# 001-0002_beaglebone_cape_board.net
KiCad netlist of a schematic drawn in Altium Designer
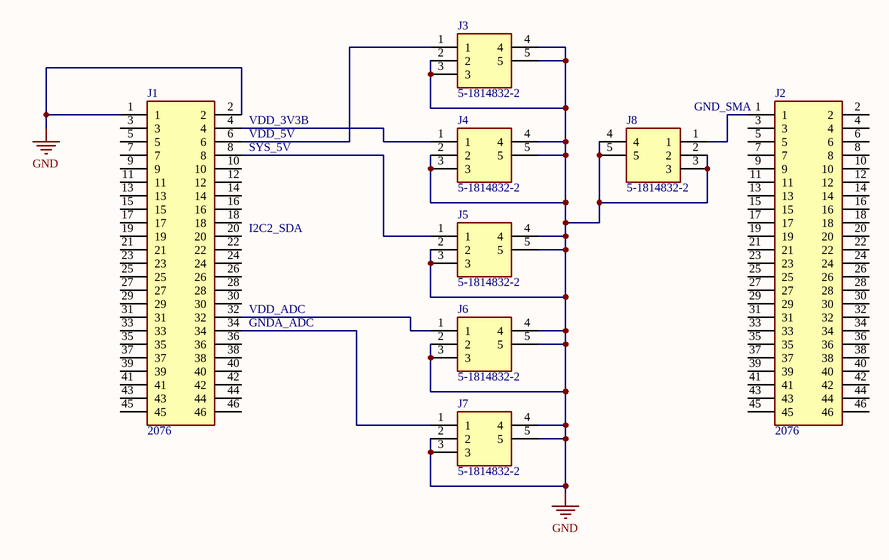
[diagram p0: 001-0002_beaglebone_cape_board.SchDoc]

(export (version "E")
  (design (tool "Eeschema 10.0.6"))
  (components
    (comp (ref "J1")
      (value "2076")
      (footprint "HDRV46W64P254_2X23_5842X500X874P")
      (description "Adafruit Accessories 2x23 Male Headers for BeagleBone Black - Two Pack")
      (fields (field (name "MOUSER PART NUMBER") "485-2076"))
      (libsource (lib "default") (part "2076"))
    )
    (comp (ref "J2")
      (value "2076")
      (footprint "HDRV46W64P254_2X23_5842X500X874P")
      (description "Adafruit Accessories 2x23 Male Headers for BeagleBone Black - Two Pack")
      (fields (field (name "MOUSER PART NUMBER") "485-2076"))
      (libsource (lib "default") (part "2076"))
    )
    (comp (ref "J3")
      (value "5-1814832-2")
      (footprint "5-1814832-2")
      (description "SMA Connector Jack, Female Socket 50 Ohms Through Hole Solder")
      (fields (field (name "MOUSER PART NUMBER") "571-5-1814832-2"))
      (libsource (lib "") (part "5-1814832-2_1"))
    )
    (comp (ref "J4")
      (value "5-1814832-2")
      (footprint "5-1814832-2")
      (description "SMA Connector Jack, Female Socket 50 Ohms Through Hole Solder")
      (fields (field (name "MOUSER PART NUMBER") "571-5-1814832-2"))
      (libsource (lib "") (part "5-1814832-2_1"))
    )
    (comp (ref "J5")
      (value "5-1814832-2")
      (footprint "5-1814832-2")
      (description "SMA Connector Jack, Female Socket 50 Ohms Through Hole Solder")
      (fields (field (name "MOUSER PART NUMBER") "571-5-1814832-2"))
      (libsource (lib "") (part "5-1814832-2_1"))
    )
    (comp (ref "J6")
      (value "5-1814832-2")
      (footprint "5-1814832-2")
      (description "SMA Connector Jack, Female Socket 50 Ohms Through Hole Solder")
      (fields (field (name "MOUSER PART NUMBER") "571-5-1814832-2"))
      (libsource (lib "") (part "5-1814832-2_1"))
    )
    (comp (ref "J7")
      (value "5-1814832-2")
      (footprint "5-1814832-2")
      (description "SMA Connector Jack, Female Socket 50 Ohms Through Hole Solder")
      (fields (field (name "MOUSER PART NUMBER") "571-5-1814832-2"))
      (libsource (lib "") (part "5-1814832-2_1"))
    )
    (comp (ref "J8")
      (value "5-1814832-2")
      (footprint "5-1814832-2")
      (description "SMA Connector Jack, Female Socket 50 Ohms Through Hole Solder")
      (fields (field (name "MOUSER PART NUMBER") "571-5-1814832-2"))
      (libsource (lib "default") (part "5-1814832-2"))
    )
  )
  (nets
    (net (code "1") (name "GND") (class "Default")
      (node (ref "J1") (pin "1") (pinfunction "1_1") (pintype "passive"))
      (node (ref "J1") (pin "2") (pinfunction "2_2") (pintype "passive"))
      (node (ref "J3") (pin "2") (pinfunction "2_2") (pintype "passive"))
      (node (ref "J3") (pin "3") (pinfunction "3_3") (pintype "passive"))
      (node (ref "J3") (pin "4") (pinfunction "4_4") (pintype "passive"))
      (node (ref "J3") (pin "5") (pinfunction "5_5") (pintype "passive"))
      (node (ref "J4") (pin "2") (pinfunction "2_2") (pintype "passive"))
      (node (ref "J4") (pin "3") (pinfunction "3_3") (pintype "passive"))
      (node (ref "J4") (pin "4") (pinfunction "4_4") (pintype "passive"))
      (node (ref "J4") (pin "5") (pinfunction "5_5") (pintype "passive"))
      (node (ref "J5") (pin "2") (pinfunction "2_2") (pintype "passive"))
      (node (ref "J5") (pin "3") (pinfunction "3_3") (pintype "passive"))
      (node (ref "J5") (pin "4") (pinfunction "4_4") (pintype "passive"))
      (node (ref "J5") (pin "5") (pinfunction "5_5") (pintype "passive"))
      (node (ref "J6") (pin "2") (pinfunction "2_2") (pintype "passive"))
      (node (ref "J6") (pin "3") (pinfunction "3_3") (pintype "passive"))
      (node (ref "J6") (pin "4") (pinfunction "4_4") (pintype "passive"))
      (node (ref "J6") (pin "5") (pinfunction "5_5") (pintype "passive"))
      (node (ref "J7") (pin "2") (pinfunction "2_2") (pintype "passive"))
      (node (ref "J7") (pin "3") (pinfunction "3_3") (pintype "passive"))
      (node (ref "J7") (pin "4") (pinfunction "4_4") (pintype "passive"))
      (node (ref "J7") (pin "5") (pinfunction "5_5") (pintype "passive"))
      (node (ref "J8") (pin "2") (pinfunction "2_2") (pintype "passive"))
      (node (ref "J8") (pin "3") (pinfunction "3_3") (pintype "passive"))
      (node (ref "J8") (pin "4") (pinfunction "4_4") (pintype "passive"))
      (node (ref "J8") (pin "5") (pinfunction "5_5") (pintype "passive"))
    )
    (net (code "2") (name "Net-(J1-Pad4)") (class "Default")
      (node (ref "J1") (pin "4") (pinfunction "4_4") (pintype "passive"))
      (node (ref "J4") (pin "1") (pinfunction "1_1") (pintype "passive"))
    )
    (net (code "3") (name "Net-(J1-Pad6)") (class "Default")
      (node (ref "J1") (pin "6") (pinfunction "6_6") (pintype "passive"))
      (node (ref "J3") (pin "1") (pinfunction "1_1") (pintype "passive"))
    )
    (net (code "4") (name "Net-(J1-Pad8)") (class "Default")
      (node (ref "J1") (pin "8") (pinfunction "8_8") (pintype "passive"))
      (node (ref "J5") (pin "1") (pinfunction "1_1") (pintype "passive"))
    )
    (net (code "5") (name "Net-(J1-Pad32)") (class "Default")
      (node (ref "J1") (pin "32") (pinfunction "32_32") (pintype "passive"))
      (node (ref "J6") (pin "1") (pinfunction "1_1") (pintype "passive"))
    )
    (net (code "6") (name "Net-(J1-Pad34)") (class "Default")
      (node (ref "J1") (pin "34") (pinfunction "34_34") (pintype "passive"))
      (node (ref "J7") (pin "1") (pinfunction "1_1") (pintype "passive"))
    )
    (net (code "7") (name "Net-(J2-Pad1)") (class "Default")
      (node (ref "J2") (pin "1") (pinfunction "1_1") (pintype "passive"))
      (node (ref "J8") (pin "1") (pinfunction "1_1") (pintype "passive"))
    )
    (net (code "8") (name "unconnected-(J1-Pad3)") (class "Default")
      (node (ref "J1") (pin "3") (pinfunction "3_3") (pintype "passive"))
    )
    (net (code "9") (name "unconnected-(J1-Pad5)") (class "Default")
      (node (ref "J1") (pin "5") (pinfunction "5_5") (pintype "passive"))
    )
    (net (code "10") (name "unconnected-(J1-Pad7)") (class "Default")
      (node (ref "J1") (pin "7") (pinfunction "7_7") (pintype "passive"))
    )
    (net (code "11") (name "unconnected-(J1-Pad9)") (class "Default")
      (node (ref "J1") (pin "9") (pinfunction "9_9") (pintype "passive"))
    )
    (net (code "12") (name "unconnected-(J1-Pad10)") (class "Default")
      (node (ref "J1") (pin "10") (pinfunction "10_10") (pintype "passive"))
    )
    (net (code "13") (name "unconnected-(J1-Pad11)") (class "Default")
      (node (ref "J1") (pin "11") (pinfunction "11_11") (pintype "passive"))
    )
    (net (code "14") (name "unconnected-(J1-Pad12)") (class "Default")
      (node (ref "J1") (pin "12") (pinfunction "12_12") (pintype "passive"))
    )
    (net (code "15") (name "unconnected-(J1-Pad13)") (class "Default")
      (node (ref "J1") (pin "13") (pinfunction "13_13") (pintype "passive"))
    )
    (net (code "16") (name "unconnected-(J1-Pad14)") (class "Default")
      (node (ref "J1") (pin "14") (pinfunction "14_14") (pintype "passive"))
    )
    (net (code "17") (name "unconnected-(J1-Pad15)") (class "Default")
      (node (ref "J1") (pin "15") (pinfunction "15_15") (pintype "passive"))
    )
    (net (code "18") (name "unconnected-(J1-Pad16)") (class "Default")
      (node (ref "J1") (pin "16") (pinfunction "16_16") (pintype "passive"))
    )
    (net (code "19") (name "unconnected-(J1-Pad17)") (class "Default")
      (node (ref "J1") (pin "17") (pinfunction "17_17") (pintype "passive"))
    )
    (net (code "20") (name "unconnected-(J1-Pad18)") (class "Default")
      (node (ref "J1") (pin "18") (pinfunction "18_18") (pintype "passive"))
    )
    (net (code "21") (name "unconnected-(J1-Pad19)") (class "Default")
      (node (ref "J1") (pin "19") (pinfunction "19_19") (pintype "passive"))
    )
    (net (code "22") (name "unconnected-(J1-Pad20)") (class "Default")
      (node (ref "J1") (pin "20") (pinfunction "20_20") (pintype "passive"))
    )
    (net (code "23") (name "unconnected-(J1-Pad21)") (class "Default")
      (node (ref "J1") (pin "21") (pinfunction "21_21") (pintype "passive"))
    )
    (net (code "24") (name "unconnected-(J1-Pad22)") (class "Default")
      (node (ref "J1") (pin "22") (pinfunction "22_22") (pintype "passive"))
    )
    (net (code "25") (name "unconnected-(J1-Pad23)") (class "Default")
      (node (ref "J1") (pin "23") (pinfunction "23_23") (pintype "passive"))
    )
    (net (code "26") (name "unconnected-(J1-Pad24)") (class "Default")
      (node (ref "J1") (pin "24") (pinfunction "24_24") (pintype "passive"))
    )
    (net (code "27") (name "unconnected-(J1-Pad25)") (class "Default")
      (node (ref "J1") (pin "25") (pinfunction "25_25") (pintype "passive"))
    )
    (net (code "28") (name "unconnected-(J1-Pad26)") (class "Default")
      (node (ref "J1") (pin "26") (pinfunction "26_26") (pintype "passive"))
    )
    (net (code "29") (name "unconnected-(J1-Pad27)") (class "Default")
      (node (ref "J1") (pin "27") (pinfunction "27_27") (pintype "passive"))
    )
    (net (code "30") (name "unconnected-(J1-Pad28)") (class "Default")
      (node (ref "J1") (pin "28") (pinfunction "28_28") (pintype "passive"))
    )
    (net (code "31") (name "unconnected-(J1-Pad29)") (class "Default")
      (node (ref "J1") (pin "29") (pinfunction "29_29") (pintype "passive"))
    )
    (net (code "32") (name "unconnected-(J1-Pad30)") (class "Default")
      (node (ref "J1") (pin "30") (pinfunction "30_30") (pintype "passive"))
    )
    (net (code "33") (name "unconnected-(J1-Pad31)") (class "Default")
      (node (ref "J1") (pin "31") (pinfunction "31_31") (pintype "passive"))
    )
    (net (code "34") (name "unconnected-(J1-Pad33)") (class "Default")
      (node (ref "J1") (pin "33") (pinfunction "33_33") (pintype "passive"))
    )
    (net (code "35") (name "unconnected-(J1-Pad35)") (class "Default")
      (node (ref "J1") (pin "35") (pinfunction "35_35") (pintype "passive"))
    )
    (net (code "36") (name "unconnected-(J1-Pad36)") (class "Default")
      (node (ref "J1") (pin "36") (pinfunction "36_36") (pintype "passive"))
    )
    (net (code "37") (name "unconnected-(J1-Pad37)") (class "Default")
      (node (ref "J1") (pin "37") (pinfunction "37_37") (pintype "passive"))
    )
    (net (code "38") (name "unconnected-(J1-Pad38)") (class "Default")
      (node (ref "J1") (pin "38") (pinfunction "38_38") (pintype "passive"))
    )
    (net (code "39") (name "unconnected-(J1-Pad39)") (class "Default")
      (node (ref "J1") (pin "39") (pinfunction "39_39") (pintype "passive"))
    )
    (net (code "40") (name "unconnected-(J1-Pad40)") (class "Default")
      (node (ref "J1") (pin "40") (pinfunction "40_40") (pintype "passive"))
    )
    (net (code "41") (name "unconnected-(J1-Pad41)") (class "Default")
      (node (ref "J1") (pin "41") (pinfunction "41_41") (pintype "passive"))
    )
    (net (code "42") (name "unconnected-(J1-Pad42)") (class "Default")
      (node (ref "J1") (pin "42") (pinfunction "42_42") (pintype "passive"))
    )
    (net (code "43") (name "unconnected-(J1-Pad43)") (class "Default")
      (node (ref "J1") (pin "43") (pinfunction "43_43") (pintype "passive"))
    )
    (net (code "44") (name "unconnected-(J1-Pad44)") (class "Default")
      (node (ref "J1") (pin "44") (pinfunction "44_44") (pintype "passive"))
    )
    (net (code "45") (name "unconnected-(J1-Pad45)") (class "Default")
      (node (ref "J1") (pin "45") (pinfunction "45_45") (pintype "passive"))
    )
    (net (code "46") (name "unconnected-(J1-Pad46)") (class "Default")
      (node (ref "J1") (pin "46") (pinfunction "46_46") (pintype "passive"))
    )
    (net (code "47") (name "unconnected-(J2-Pad2)") (class "Default")
      (node (ref "J2") (pin "2") (pinfunction "2_2") (pintype "passive"))
    )
    (net (code "48") (name "unconnected-(J2-Pad3)") (class "Default")
      (node (ref "J2") (pin "3") (pinfunction "3_3") (pintype "passive"))
    )
    (net (code "49") (name "unconnected-(J2-Pad4)") (class "Default")
      (node (ref "J2") (pin "4") (pinfunction "4_4") (pintype "passive"))
    )
    (net (code "50") (name "unconnected-(J2-Pad5)") (class "Default")
      (node (ref "J2") (pin "5") (pinfunction "5_5") (pintype "passive"))
    )
    (net (code "51") (name "unconnected-(J2-Pad6)") (class "Default")
      (node (ref "J2") (pin "6") (pinfunction "6_6") (pintype "passive"))
    )
    (net (code "52") (name "unconnected-(J2-Pad7)") (class "Default")
      (node (ref "J2") (pin "7") (pinfunction "7_7") (pintype "passive"))
    )
    (net (code "53") (name "unconnected-(J2-Pad8)") (class "Default")
      (node (ref "J2") (pin "8") (pinfunction "8_8") (pintype "passive"))
    )
    (net (code "54") (name "unconnected-(J2-Pad9)") (class "Default")
      (node (ref "J2") (pin "9") (pinfunction "9_9") (pintype "passive"))
    )
    (net (code "55") (name "unconnected-(J2-Pad10)") (class "Default")
      (node (ref "J2") (pin "10") (pinfunction "10_10") (pintype "passive"))
    )
    (net (code "56") (name "unconnected-(J2-Pad11)") (class "Default")
      (node (ref "J2") (pin "11") (pinfunction "11_11") (pintype "passive"))
    )
    (net (code "57") (name "unconnected-(J2-Pad12)") (class "Default")
      (node (ref "J2") (pin "12") (pinfunction "12_12") (pintype "passive"))
    )
    (net (code "58") (name "unconnected-(J2-Pad13)") (class "Default")
      (node (ref "J2") (pin "13") (pinfunction "13_13") (pintype "passive"))
    )
    (net (code "59") (name "unconnected-(J2-Pad14)") (class "Default")
      (node (ref "J2") (pin "14") (pinfunction "14_14") (pintype "passive"))
    )
    (net (code "60") (name "unconnected-(J2-Pad15)") (class "Default")
      (node (ref "J2") (pin "15") (pinfunction "15_15") (pintype "passive"))
    )
    (net (code "61") (name "unconnected-(J2-Pad16)") (class "Default")
      (node (ref "J2") (pin "16") (pinfunction "16_16") (pintype "passive"))
    )
    (net (code "62") (name "unconnected-(J2-Pad17)") (class "Default")
      (node (ref "J2") (pin "17") (pinfunction "17_17") (pintype "passive"))
    )
    (net (code "63") (name "unconnected-(J2-Pad18)") (class "Default")
      (node (ref "J2") (pin "18") (pinfunction "18_18") (pintype "passive"))
    )
    (net (code "64") (name "unconnected-(J2-Pad19)") (class "Default")
      (node (ref "J2") (pin "19") (pinfunction "19_19") (pintype "passive"))
    )
    (net (code "65") (name "unconnected-(J2-Pad20)") (class "Default")
      (node (ref "J2") (pin "20") (pinfunction "20_20") (pintype "passive"))
    )
    (net (code "66") (name "unconnected-(J2-Pad21)") (class "Default")
      (node (ref "J2") (pin "21") (pinfunction "21_21") (pintype "passive"))
    )
    (net (code "67") (name "unconnected-(J2-Pad22)") (class "Default")
      (node (ref "J2") (pin "22") (pinfunction "22_22") (pintype "passive"))
    )
    (net (code "68") (name "unconnected-(J2-Pad23)") (class "Default")
      (node (ref "J2") (pin "23") (pinfunction "23_23") (pintype "passive"))
    )
    (net (code "69") (name "unconnected-(J2-Pad24)") (class "Default")
      (node (ref "J2") (pin "24") (pinfunction "24_24") (pintype "passive"))
    )
    (net (code "70") (name "unconnected-(J2-Pad25)") (class "Default")
      (node (ref "J2") (pin "25") (pinfunction "25_25") (pintype "passive"))
    )
    (net (code "71") (name "unconnected-(J2-Pad26)") (class "Default")
      (node (ref "J2") (pin "26") (pinfunction "26_26") (pintype "passive"))
    )
    (net (code "72") (name "unconnected-(J2-Pad27)") (class "Default")
      (node (ref "J2") (pin "27") (pinfunction "27_27") (pintype "passive"))
    )
    (net (code "73") (name "unconnected-(J2-Pad28)") (class "Default")
      (node (ref "J2") (pin "28") (pinfunction "28_28") (pintype "passive"))
    )
    (net (code "74") (name "unconnected-(J2-Pad29)") (class "Default")
      (node (ref "J2") (pin "29") (pinfunction "29_29") (pintype "passive"))
    )
    (net (code "75") (name "unconnected-(J2-Pad30)") (class "Default")
      (node (ref "J2") (pin "30") (pinfunction "30_30") (pintype "passive"))
    )
    (net (code "76") (name "unconnected-(J2-Pad31)") (class "Default")
      (node (ref "J2") (pin "31") (pinfunction "31_31") (pintype "passive"))
    )
    (net (code "77") (name "unconnected-(J2-Pad32)") (class "Default")
      (node (ref "J2") (pin "32") (pinfunction "32_32") (pintype "passive"))
    )
    (net (code "78") (name "unconnected-(J2-Pad33)") (class "Default")
      (node (ref "J2") (pin "33") (pinfunction "33_33") (pintype "passive"))
    )
    (net (code "79") (name "unconnected-(J2-Pad34)") (class "Default")
      (node (ref "J2") (pin "34") (pinfunction "34_34") (pintype "passive"))
    )
    (net (code "80") (name "unconnected-(J2-Pad35)") (class "Default")
      (node (ref "J2") (pin "35") (pinfunction "35_35") (pintype "passive"))
    )
    (net (code "81") (name "unconnected-(J2-Pad36)") (class "Default")
      (node (ref "J2") (pin "36") (pinfunction "36_36") (pintype "passive"))
    )
    (net (code "82") (name "unconnected-(J2-Pad37)") (class "Default")
      (node (ref "J2") (pin "37") (pinfunction "37_37") (pintype "passive"))
    )
    (net (code "83") (name "unconnected-(J2-Pad38)") (class "Default")
      (node (ref "J2") (pin "38") (pinfunction "38_38") (pintype "passive"))
    )
    (net (code "84") (name "unconnected-(J2-Pad39)") (class "Default")
      (node (ref "J2") (pin "39") (pinfunction "39_39") (pintype "passive"))
    )
    (net (code "85") (name "unconnected-(J2-Pad40)") (class "Default")
      (node (ref "J2") (pin "40") (pinfunction "40_40") (pintype "passive"))
    )
    (net (code "86") (name "unconnected-(J2-Pad41)") (class "Default")
      (node (ref "J2") (pin "41") (pinfunction "41_41") (pintype "passive"))
    )
    (net (code "87") (name "unconnected-(J2-Pad42)") (class "Default")
      (node (ref "J2") (pin "42") (pinfunction "42_42") (pintype "passive"))
    )
    (net (code "88") (name "unconnected-(J2-Pad43)") (class "Default")
      (node (ref "J2") (pin "43") (pinfunction "43_43") (pintype "passive"))
    )
    (net (code "89") (name "unconnected-(J2-Pad44)") (class "Default")
      (node (ref "J2") (pin "44") (pinfunction "44_44") (pintype "passive"))
    )
    (net (code "90") (name "unconnected-(J2-Pad45)") (class "Default")
      (node (ref "J2") (pin "45") (pinfunction "45_45") (pintype "passive"))
    )
    (net (code "91") (name "unconnected-(J2-Pad46)") (class "Default")
      (node (ref "J2") (pin "46") (pinfunction "46_46") (pintype "passive"))
    )
  )
)
